# Esquema.net
KiCad netlist of a schematic drawn in EAGLE
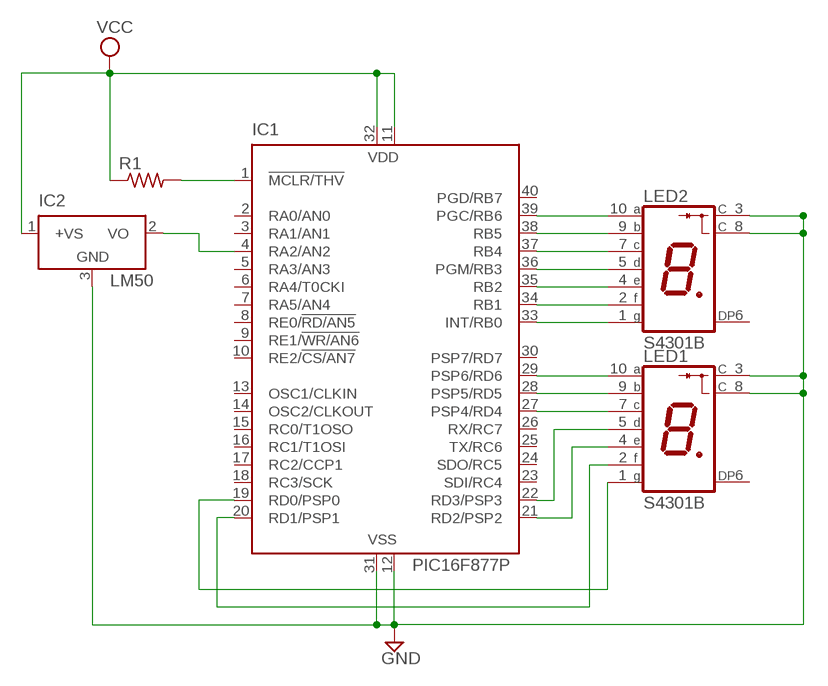
[diagram p0: schematic, sheet 1]

(export (version "E")
  (design (tool "Eeschema 10.0.6"))
  (components
    (comp (ref "IC1")
      (value "PIC16F877P")
      (footprint "eagle-import:DIL40")
      (fields (field (name "MF") "MICROCHIP") (field (name "MPN") "PIC16F877-04/P"))
      (libsource (lib "eagle-import") (part "PIC16F87P7"))
    )
    (comp (ref "IC2")
      (value "LM50")
      (footprint "eagle-import:SOT23")
      (libsource (lib "eagle-import") (part "LM50"))
    )
    (comp (ref "LED1")
      (value "S4301B")
      (footprint "eagle-import:S4301B")
      (libsource (lib "eagle-import") (part "S4301B"))
    )
    (comp (ref "LED2")
      (value "S4301B")
      (footprint "eagle-import:S4301B")
      (libsource (lib "eagle-import") (part "S4301B"))
    )
    (comp (ref "R1")
      (value "R-US_0204/2V")
      (footprint "eagle-import:0204V")
      (libsource (lib "eagle-import") (part "R-US_0204/2V"))
    )
  )
  (nets
    (net (code "1") (name "GND") (class "Default")
      (node (ref "IC1") (pin "12") (pinfunction "VSS_12") (pintype "power_in"))
      (node (ref "IC1") (pin "31") (pinfunction "VSS_31") (pintype "power_in"))
      (node (ref "IC2") (pin "3") (pinfunction "GND_3") (pintype "power_in"))
      (node (ref "LED1") (pin "3") (pinfunction "C_3") (pintype "passive"))
      (node (ref "LED1") (pin "8") (pinfunction "C_8") (pintype "passive"))
      (node (ref "LED2") (pin "3") (pinfunction "C_3") (pintype "passive"))
      (node (ref "LED2") (pin "8") (pinfunction "C_8") (pintype "passive"))
    )
    (net (code "2") (name "Net-(IC1-INT{slash}RB0)") (class "Default")
      (node (ref "IC1") (pin "33") (pinfunction "INT/RB0_33") (pintype "bidirectional"))
      (node (ref "LED2") (pin "1") (pinfunction "G_1") (pintype "passive"))
    )
    (net (code "3") (name "Net-(IC1-PGC{slash}RB6)") (class "Default")
      (node (ref "IC1") (pin "39") (pinfunction "PGC/RB6_39") (pintype "bidirectional"))
      (node (ref "LED2") (pin "10") (pinfunction "A_10") (pintype "passive"))
    )
    (net (code "4") (name "Net-(IC1-PGM{slash}RB3)") (class "Default")
      (node (ref "IC1") (pin "36") (pinfunction "PGM/RB3_36") (pintype "bidirectional"))
      (node (ref "LED2") (pin "5") (pinfunction "D_5") (pintype "passive"))
    )
    (net (code "5") (name "Net-(IC1-PSP4{slash}RD4)") (class "Default")
      (node (ref "IC1") (pin "27") (pinfunction "PSP4/RD4_27") (pintype "bidirectional"))
      (node (ref "LED1") (pin "7") (pinfunction "C_7") (pintype "passive"))
    )
    (net (code "6") (name "Net-(IC1-PSP5{slash}RD5)") (class "Default")
      (node (ref "IC1") (pin "28") (pinfunction "PSP5/RD5_28") (pintype "bidirectional"))
      (node (ref "LED1") (pin "9") (pinfunction "B_9") (pintype "passive"))
    )
    (net (code "7") (name "Net-(IC1-PSP6{slash}RD6)") (class "Default")
      (node (ref "IC1") (pin "29") (pinfunction "PSP6/RD6_29") (pintype "bidirectional"))
      (node (ref "LED1") (pin "10") (pinfunction "A_10") (pintype "passive"))
    )
    (net (code "8") (name "Net-(IC1-RA2{slash}AN2)") (class "Default")
      (node (ref "IC1") (pin "4") (pinfunction "RA2/AN2_4") (pintype "bidirectional"))
      (node (ref "IC2") (pin "2") (pinfunction "VO_2") (pintype "input"))
    )
    (net (code "9") (name "Net-(IC1-RB1)") (class "Default")
      (node (ref "IC1") (pin "34") (pinfunction "RB1_34") (pintype "bidirectional"))
      (node (ref "LED2") (pin "2") (pinfunction "F_2") (pintype "passive"))
    )
    (net (code "10") (name "Net-(IC1-RB2)") (class "Default")
      (node (ref "IC1") (pin "35") (pinfunction "RB2_35") (pintype "bidirectional"))
      (node (ref "LED2") (pin "4") (pinfunction "E_4") (pintype "passive"))
    )
    (net (code "11") (name "Net-(IC1-RB4)") (class "Default")
      (node (ref "IC1") (pin "37") (pinfunction "RB4_37") (pintype "bidirectional"))
      (node (ref "LED2") (pin "7") (pinfunction "C_7") (pintype "passive"))
    )
    (net (code "12") (name "Net-(IC1-RB5)") (class "Default")
      (node (ref "IC1") (pin "38") (pinfunction "RB5_38") (pintype "bidirectional"))
      (node (ref "LED2") (pin "9") (pinfunction "B_9") (pintype "passive"))
    )
    (net (code "13") (name "Net-(IC1-RD0{slash}PSP0)") (class "Default")
      (node (ref "IC1") (pin "19") (pinfunction "RD0/PSP0_19") (pintype "bidirectional"))
      (node (ref "LED1") (pin "1") (pinfunction "G_1") (pintype "passive"))
    )
    (net (code "14") (name "Net-(IC1-RD1{slash}PSP1)") (class "Default")
      (node (ref "IC1") (pin "20") (pinfunction "RD1/PSP1_20") (pintype "bidirectional"))
      (node (ref "LED1") (pin "2") (pinfunction "F_2") (pintype "passive"))
    )
    (net (code "15") (name "Net-(IC1-RD2{slash}PSP2)") (class "Default")
      (node (ref "IC1") (pin "21") (pinfunction "RD2/PSP2_21") (pintype "bidirectional"))
      (node (ref "LED1") (pin "4") (pinfunction "E_4") (pintype "passive"))
    )
    (net (code "16") (name "Net-(IC1-RD3{slash}PSP3)") (class "Default")
      (node (ref "IC1") (pin "22") (pinfunction "RD3/PSP3_22") (pintype "bidirectional"))
      (node (ref "LED1") (pin "5") (pinfunction "D_5") (pintype "passive"))
    )
    (net (code "17") (name "Net-(IC1-~{MCLR{slash}THV})") (class "Default")
      (node (ref "IC1") (pin "1") (pinfunction "~{MCLR/THV}_1") (pintype "input"))
      (node (ref "R1") (pin "2") (pinfunction "2_2") (pintype "passive"))
    )
    (net (code "18") (name "VCC") (class "Default")
      (node (ref "IC1") (pin "11") (pinfunction "VDD_11") (pintype "power_in"))
      (node (ref "IC1") (pin "32") (pinfunction "VDD_32") (pintype "power_in"))
      (node (ref "IC2") (pin "1") (pinfunction "+VS_1") (pintype "input"))
      (node (ref "R1") (pin "1") (pinfunction "1_1") (pintype "passive"))
    )
    (net (code "19") (name "unconnected-(IC1-OSC1{slash}CLKIN-Pad13)") (class "Default")
      (node (ref "IC1") (pin "13") (pinfunction "OSC1/CLKIN_13") (pintype "input"))
    )
    (net (code "20") (name "unconnected-(IC1-OSC2{slash}CLKOUT-Pad14)") (class "Default")
      (node (ref "IC1") (pin "14") (pinfunction "OSC2/CLKOUT_14") (pintype "output"))
    )
    (net (code "21") (name "unconnected-(IC1-PGD{slash}RB7-Pad40)") (class "Default")
      (node (ref "IC1") (pin "40") (pinfunction "PGD/RB7_40") (pintype "bidirectional"))
    )
    (net (code "22") (name "unconnected-(IC1-PSP7{slash}RD7-Pad30)") (class "Default")
      (node (ref "IC1") (pin "30") (pinfunction "PSP7/RD7_30") (pintype "bidirectional"))
    )
    (net (code "23") (name "unconnected-(IC1-RA0{slash}AN0-Pad2)") (class "Default")
      (node (ref "IC1") (pin "2") (pinfunction "RA0/AN0_2") (pintype "bidirectional"))
    )
    (net (code "24") (name "unconnected-(IC1-RA1{slash}AN1-Pad3)") (class "Default")
      (node (ref "IC1") (pin "3") (pinfunction "RA1/AN1_3") (pintype "bidirectional"))
    )
    (net (code "25") (name "unconnected-(IC1-RA3{slash}AN3-Pad5)") (class "Default")
      (node (ref "IC1") (pin "5") (pinfunction "RA3/AN3_5") (pintype "bidirectional"))
    )
    (net (code "26") (name "unconnected-(IC1-RA4{slash}T0CKI-Pad6)") (class "Default")
      (node (ref "IC1") (pin "6") (pinfunction "RA4/T0CKI_6") (pintype "bidirectional"))
    )
    (net (code "27") (name "unconnected-(IC1-RA5{slash}AN4-Pad7)") (class "Default")
      (node (ref "IC1") (pin "7") (pinfunction "RA5/AN4_7") (pintype "bidirectional"))
    )
    (net (code "28") (name "unconnected-(IC1-RC0{slash}T1OSO-Pad15)") (class "Default")
      (node (ref "IC1") (pin "15") (pinfunction "RC0/T1OSO_15") (pintype "bidirectional"))
    )
    (net (code "29") (name "unconnected-(IC1-RC1{slash}T1OSI-Pad16)") (class "Default")
      (node (ref "IC1") (pin "16") (pinfunction "RC1/T1OSI_16") (pintype "bidirectional"))
    )
    (net (code "30") (name "unconnected-(IC1-RC2{slash}CCP1-Pad17)") (class "Default")
      (node (ref "IC1") (pin "17") (pinfunction "RC2/CCP1_17") (pintype "bidirectional"))
    )
    (net (code "31") (name "unconnected-(IC1-RC3{slash}SCK-Pad18)") (class "Default")
      (node (ref "IC1") (pin "18") (pinfunction "RC3/SCK_18") (pintype "bidirectional"))
    )
    (net (code "32") (name "unconnected-(IC1-RE0{slash}~{RD{slash}AN5}-Pad8)") (class "Default")
      (node (ref "IC1") (pin "8") (pinfunction "RE0/~{RD/AN5}_8") (pintype "bidirectional"))
    )
    (net (code "33") (name "unconnected-(IC1-RE1{slash}~{WR{slash}AN6}-Pad9)") (class "Default")
      (node (ref "IC1") (pin "9") (pinfunction "RE1/~{WR/AN6}_9") (pintype "bidirectional"))
    )
    (net (code "34") (name "unconnected-(IC1-RE2{slash}~{CS{slash}AN7}-Pad10)") (class "Default")
      (node (ref "IC1") (pin "10") (pinfunction "RE2/~{CS/AN7}_10") (pintype "bidirectional"))
    )
    (net (code "35") (name "unconnected-(IC1-RX{slash}RC7-Pad26)") (class "Default")
      (node (ref "IC1") (pin "26") (pinfunction "RX/RC7_26") (pintype "bidirectional"))
    )
    (net (code "36") (name "unconnected-(IC1-SDI{slash}RC4-Pad23)") (class "Default")
      (node (ref "IC1") (pin "23") (pinfunction "SDI/RC4_23") (pintype "bidirectional"))
    )
    (net (code "37") (name "unconnected-(IC1-SDO{slash}RC5-Pad24)") (class "Default")
      (node (ref "IC1") (pin "24") (pinfunction "SDO/RC5_24") (pintype "bidirectional"))
    )
    (net (code "38") (name "unconnected-(IC1-TX{slash}RC6-Pad25)") (class "Default")
      (node (ref "IC1") (pin "25") (pinfunction "TX/RC6_25") (pintype "bidirectional"))
    )
    (net (code "39") (name "unconnected-(LED1-DP-Pad6)") (class "Default")
      (node (ref "LED1") (pin "6") (pinfunction "DP_6") (pintype "passive"))
    )
    (net (code "40") (name "unconnected-(LED2-DP-Pad6)") (class "Default")
      (node (ref "LED2") (pin "6") (pinfunction "DP_6") (pintype "passive"))
    )
  )
)
